# Wiegand.net
KiCad netlist of a schematic drawn in EAGLE
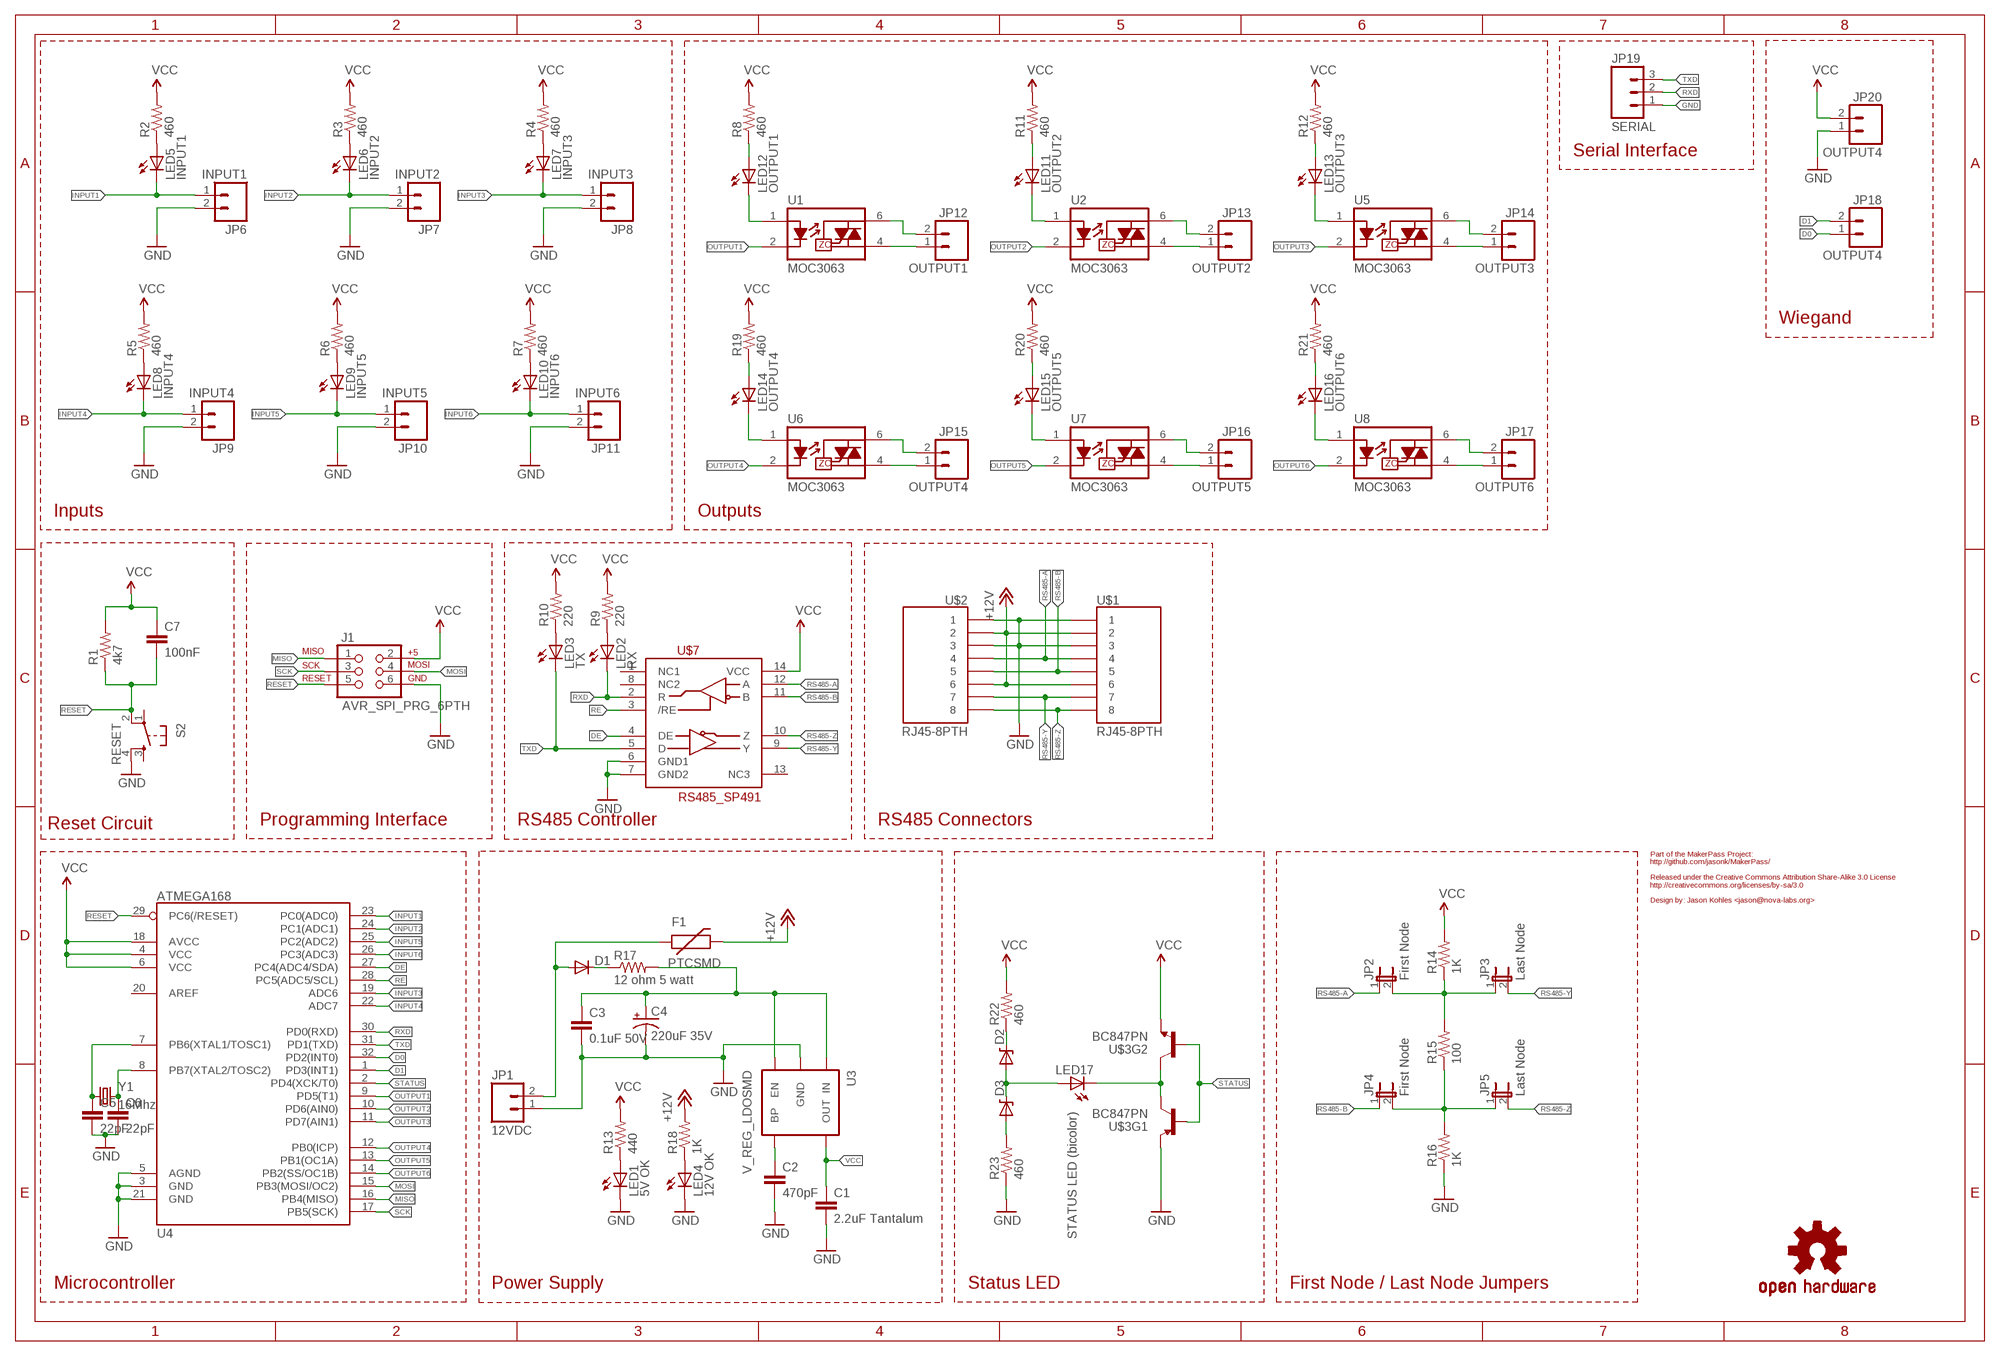
[diagram p0: schematic, sheet 1]

(export (version "E")
  (design (tool "Eeschema 10.0.6"))
  (components
    (comp (ref "C1")
      (value "2.2uF Tantalum")
      (footprint "eagle-import:0402-CAP")
      (libsource (lib "eagle-import") (part "CAP0402-CAP"))
    )
    (comp (ref "C2")
      (value "470pF")
      (footprint "eagle-import:0402-CAP")
      (libsource (lib "eagle-import") (part "CAP0402-CAP"))
    )
    (comp (ref "C3")
      (value "0.1uF 50V")
      (footprint "eagle-import:0402-CAP")
      (libsource (lib "eagle-import") (part "CAP0402-CAP"))
    )
    (comp (ref "C4")
      (value "220uF 35V")
      (footprint "eagle-import:VISHAY_C")
      (libsource (lib "eagle-import") (part "CAP_POLSMD"))
    )
    (comp (ref "C5")
      (value "22pF")
      (footprint "eagle-import:0603-CAP")
      (libsource (lib "eagle-import") (part "CAP0603-CAP"))
    )
    (comp (ref "C6")
      (value "22pF")
      (footprint "eagle-import:0603-CAP")
      (libsource (lib "eagle-import") (part "CAP0603-CAP"))
    )
    (comp (ref "C7")
      (value "100nF")
      (footprint "eagle-import:0603-CAP")
      (libsource (lib "eagle-import") (part "CAP0603-CAP"))
    )
    (comp (ref "D1")
      (value "DIODESMA")
      (footprint "eagle-import:SMA-DIODE")
      (libsource (lib "eagle-import") (part "DIODESMA"))
    )
    (comp (ref "D2")
      (value "DIODE-ZENER-BZT52")
      (footprint "eagle-import:SOD-323")
      (libsource (lib "eagle-import") (part "DIODE-ZENER-BZT52"))
    )
    (comp (ref "D3")
      (value "DIODE-ZENER-BZT52")
      (footprint "eagle-import:SOD-323")
      (libsource (lib "eagle-import") (part "DIODE-ZENER-BZT52"))
    )
    (comp (ref "F1")
      (value "PTCSMD")
      (footprint "eagle-import:PTC-1206")
      (libsource (lib "eagle-import") (part "PTCSMD"))
    )
    (comp (ref "J1")
      (value "AVR_SPI_PRG_6PTH")
      (footprint "eagle-import:2X3")
      (libsource (lib "eagle-import") (part "AVR_SPI_PRG_6PTH"))
    )
    (comp (ref "JP1")
      (value "12VDC")
      (footprint "eagle-import:SCREWTERMINAL-5MM-2")
      (libsource (lib "eagle-import") (part "M025MM"))
    )
    (comp (ref "JP2")
      (value "First Node")
      (footprint "eagle-import:1X02")
      (libsource (lib "eagle-import") (part "JUMPER-2PTH"))
    )
    (comp (ref "JP3")
      (value "Last Node")
      (footprint "eagle-import:1X02")
      (libsource (lib "eagle-import") (part "JUMPER-2PTH"))
    )
    (comp (ref "JP4")
      (value "First Node")
      (footprint "eagle-import:1X02")
      (libsource (lib "eagle-import") (part "JUMPER-2PTH"))
    )
    (comp (ref "JP5")
      (value "Last Node")
      (footprint "eagle-import:1X02")
      (libsource (lib "eagle-import") (part "JUMPER-2PTH"))
    )
    (comp (ref "JP6")
      (value "INPUT1")
      (footprint "eagle-import:SCREWTERMINAL-3.5MM-2")
      (libsource (lib "eagle-import") (part "M023.5MM"))
    )
    (comp (ref "JP7")
      (value "INPUT2")
      (footprint "eagle-import:SCREWTERMINAL-3.5MM-2")
      (libsource (lib "eagle-import") (part "M023.5MM"))
    )
    (comp (ref "JP8")
      (value "INPUT3")
      (footprint "eagle-import:SCREWTERMINAL-3.5MM-2")
      (libsource (lib "eagle-import") (part "M023.5MM"))
    )
    (comp (ref "JP9")
      (value "INPUT4")
      (footprint "eagle-import:SCREWTERMINAL-3.5MM-2")
      (libsource (lib "eagle-import") (part "M023.5MM"))
    )
    (comp (ref "JP10")
      (value "INPUT5")
      (footprint "eagle-import:SCREWTERMINAL-3.5MM-2")
      (libsource (lib "eagle-import") (part "M023.5MM"))
    )
    (comp (ref "JP11")
      (value "INPUT6")
      (footprint "eagle-import:SCREWTERMINAL-3.5MM-2")
      (libsource (lib "eagle-import") (part "M023.5MM"))
    )
    (comp (ref "JP12")
      (value "OUTPUT1")
      (footprint "eagle-import:SCREWTERMINAL-3.5MM-2")
      (libsource (lib "eagle-import") (part "M023.5MM"))
    )
    (comp (ref "JP13")
      (value "OUTPUT2")
      (footprint "eagle-import:SCREWTERMINAL-3.5MM-2")
      (libsource (lib "eagle-import") (part "M023.5MM"))
    )
    (comp (ref "JP14")
      (value "OUTPUT3")
      (footprint "eagle-import:SCREWTERMINAL-3.5MM-2")
      (libsource (lib "eagle-import") (part "M023.5MM"))
    )
    (comp (ref "JP15")
      (value "OUTPUT4")
      (footprint "eagle-import:SCREWTERMINAL-3.5MM-2")
      (libsource (lib "eagle-import") (part "M023.5MM"))
    )
    (comp (ref "JP16")
      (value "OUTPUT5")
      (footprint "eagle-import:SCREWTERMINAL-3.5MM-2")
      (libsource (lib "eagle-import") (part "M023.5MM"))
    )
    (comp (ref "JP17")
      (value "OUTPUT6")
      (footprint "eagle-import:SCREWTERMINAL-3.5MM-2")
      (libsource (lib "eagle-import") (part "M023.5MM"))
    )
    (comp (ref "JP18")
      (value "OUTPUT4")
      (footprint "eagle-import:SCREWTERMINAL-3.5MM-2")
      (libsource (lib "eagle-import") (part "M023.5MM"))
    )
    (comp (ref "JP19")
      (value "SERIAL")
      (footprint "eagle-import:1X03")
      (libsource (lib "eagle-import") (part "M03PTH"))
    )
    (comp (ref "JP20")
      (value "OUTPUT4")
      (footprint "eagle-import:SCREWTERMINAL-3.5MM-2")
      (libsource (lib "eagle-import") (part "M023.5MM"))
    )
    (comp (ref "LED1")
      (value "5V OK")
      (footprint "eagle-import:LED-1206")
      (libsource (lib "eagle-import") (part "LED1206"))
    )
    (comp (ref "LED2")
      (value "RX")
      (footprint "eagle-import:LED-1206")
      (libsource (lib "eagle-import") (part "LED1206"))
    )
    (comp (ref "LED3")
      (value "TX")
      (footprint "eagle-import:LED-1206")
      (libsource (lib "eagle-import") (part "LED1206"))
    )
    (comp (ref "LED4")
      (value "12V OK")
      (footprint "eagle-import:LED-1206")
      (libsource (lib "eagle-import") (part "LED1206"))
    )
    (comp (ref "LED5")
      (value "INPUT1")
      (footprint "eagle-import:LED-1206")
      (libsource (lib "eagle-import") (part "LED1206"))
    )
    (comp (ref "LED6")
      (value "INPUT2")
      (footprint "eagle-import:LED-1206")
      (libsource (lib "eagle-import") (part "LED1206"))
    )
    (comp (ref "LED7")
      (value "INPUT3")
      (footprint "eagle-import:LED-1206")
      (libsource (lib "eagle-import") (part "LED1206"))
    )
    (comp (ref "LED8")
      (value "INPUT4")
      (footprint "eagle-import:LED-1206")
      (libsource (lib "eagle-import") (part "LED1206"))
    )
    (comp (ref "LED9")
      (value "INPUT5")
      (footprint "eagle-import:LED-1206")
      (libsource (lib "eagle-import") (part "LED1206"))
    )
    (comp (ref "LED10")
      (value "INPUT6")
      (footprint "eagle-import:LED-1206")
      (libsource (lib "eagle-import") (part "LED1206"))
    )
    (comp (ref "LED11")
      (value "OUTPUT2")
      (footprint "eagle-import:LED-1206")
      (libsource (lib "eagle-import") (part "LED1206"))
    )
    (comp (ref "LED12")
      (value "OUTPUT1")
      (footprint "eagle-import:LED-1206")
      (libsource (lib "eagle-import") (part "LED1206"))
    )
    (comp (ref "LED13")
      (value "OUTPUT3")
      (footprint "eagle-import:LED-1206")
      (libsource (lib "eagle-import") (part "LED1206"))
    )
    (comp (ref "LED14")
      (value "OUTPUT4")
      (footprint "eagle-import:LED-1206")
      (libsource (lib "eagle-import") (part "LED1206"))
    )
    (comp (ref "LED15")
      (value "OUTPUT5")
      (footprint "eagle-import:LED-1206")
      (libsource (lib "eagle-import") (part "LED1206"))
    )
    (comp (ref "LED16")
      (value "OUTPUT6")
      (footprint "eagle-import:LED-1206")
      (libsource (lib "eagle-import") (part "LED1206"))
    )
    (comp (ref "LED17")
      (value "STATUS LED (bicolor)")
      (footprint "eagle-import:LED-1206")
      (libsource (lib "eagle-import") (part "LED1206"))
    )
    (comp (ref "LOGO1")
      (value "OSHW-LOGOM")
      (footprint "eagle-import:OSHW-LOGO-M")
      (libsource (lib "eagle-import") (part "OSHW-LOGOM"))
    )
    (comp (ref "R1")
      (value "4k7")
      (footprint "eagle-import:0603-RES")
      (libsource (lib "eagle-import") (part "RESISTOR0603-RES"))
    )
    (comp (ref "R2")
      (value "460")
      (footprint "eagle-import:0603-RES")
      (libsource (lib "eagle-import") (part "RESISTOR0603-RES"))
    )
    (comp (ref "R3")
      (value "460")
      (footprint "eagle-import:0603-RES")
      (libsource (lib "eagle-import") (part "RESISTOR0603-RES"))
    )
    (comp (ref "R4")
      (value "460")
      (footprint "eagle-import:0603-RES")
      (libsource (lib "eagle-import") (part "RESISTOR0603-RES"))
    )
    (comp (ref "R5")
      (value "460")
      (footprint "eagle-import:0603-RES")
      (libsource (lib "eagle-import") (part "RESISTOR0603-RES"))
    )
    (comp (ref "R6")
      (value "460")
      (footprint "eagle-import:0603-RES")
      (libsource (lib "eagle-import") (part "RESISTOR0603-RES"))
    )
    (comp (ref "R7")
      (value "460")
      (footprint "eagle-import:0603-RES")
      (libsource (lib "eagle-import") (part "RESISTOR0603-RES"))
    )
    (comp (ref "R8")
      (value "460")
      (footprint "eagle-import:0603-RES")
      (libsource (lib "eagle-import") (part "RESISTOR0603-RES"))
    )
    (comp (ref "R9")
      (value "220")
      (footprint "eagle-import:0603-RES")
      (libsource (lib "eagle-import") (part "RESISTOR0603-RES"))
    )
    (comp (ref "R10")
      (value "220")
      (footprint "eagle-import:0603-RES")
      (libsource (lib "eagle-import") (part "RESISTOR0603-RES"))
    )
    (comp (ref "R11")
      (value "460")
      (footprint "eagle-import:0603-RES")
      (libsource (lib "eagle-import") (part "RESISTOR0603-RES"))
    )
    (comp (ref "R12")
      (value "460")
      (footprint "eagle-import:0603-RES")
      (libsource (lib "eagle-import") (part "RESISTOR0603-RES"))
    )
    (comp (ref "R13")
      (value "440")
      (footprint "eagle-import:0603-RES")
      (libsource (lib "eagle-import") (part "RESISTOR0603-RES"))
    )
    (comp (ref "R14")
      (value "1K")
      (footprint "eagle-import:0603-RES")
      (libsource (lib "eagle-import") (part "RESISTOR0603-RES"))
    )
    (comp (ref "R15")
      (value "100")
      (footprint "eagle-import:0603-RES")
      (libsource (lib "eagle-import") (part "RESISTOR0603-RES"))
    )
    (comp (ref "R16")
      (value "1K")
      (footprint "eagle-import:0603-RES")
      (libsource (lib "eagle-import") (part "RESISTOR0603-RES"))
    )
    (comp (ref "R17")
      (value "12 ohm 5 watt")
      (footprint "eagle-import:0603-RES")
      (libsource (lib "eagle-import") (part "RESISTOR0603-RES"))
    )
    (comp (ref "R18")
      (value "1K")
      (footprint "eagle-import:0603-RES")
      (libsource (lib "eagle-import") (part "RESISTOR0603-RES"))
    )
    (comp (ref "R19")
      (value "460")
      (footprint "eagle-import:0603-RES")
      (libsource (lib "eagle-import") (part "RESISTOR0603-RES"))
    )
    (comp (ref "R20")
      (value "460")
      (footprint "eagle-import:0603-RES")
      (libsource (lib "eagle-import") (part "RESISTOR0603-RES"))
    )
    (comp (ref "R21")
      (value "460")
      (footprint "eagle-import:0603-RES")
      (libsource (lib "eagle-import") (part "RESISTOR0603-RES"))
    )
    (comp (ref "R22")
      (value "460")
      (footprint "eagle-import:0603-RES")
      (libsource (lib "eagle-import") (part "RESISTOR0603-RES"))
    )
    (comp (ref "R23")
      (value "460")
      (footprint "eagle-import:0603-RES")
      (libsource (lib "eagle-import") (part "RESISTOR0603-RES"))
    )
    (comp (ref "S2")
      (value "RESET")
      (footprint "eagle-import:TACTILE_SWITCH_SMD")
      (libsource (lib "eagle-import") (part "TAC_SWITCHSMD"))
    )
    (comp (ref "U$1")
      (value "RJ45-8PTH")
      (footprint "eagle-import:RJ45-8")
      (libsource (lib "eagle-import") (part "RJ45-8PTH"))
    )
    (comp (ref "U$2")
      (value "RJ45-8PTH")
      (footprint "eagle-import:RJ45-8")
      (libsource (lib "eagle-import") (part "RJ45-8PTH"))
    )
    (comp (ref "U$3")
      (value "BC847PN")
      (footprint "eagle-import:SOT363")
      (libsource (lib "eagle-import") (part "BC847PN"))
    )
    (comp (ref "U$7")
      (value "RS485_SP491")
      (footprint "eagle-import:SOIC-14")
      (libsource (lib "eagle-import") (part "RS485_SP491"))
    )
    (comp (ref "U1")
      (value "MOC3063")
      (footprint "eagle-import:DIP8SMD")
      (libsource (lib "eagle-import") (part "MOC3063S"))
    )
    (comp (ref "U2")
      (value "MOC3063")
      (footprint "eagle-import:DIP8SMD")
      (libsource (lib "eagle-import") (part "MOC3063S"))
    )
    (comp (ref "U3")
      (value "V_REG_LDOSMD")
      (footprint "eagle-import:SOT23-5")
      (libsource (lib "eagle-import") (part "V_REG_LDOSMD"))
    )
    (comp (ref "U4")
      (value "ATMEGA168")
      (footprint "eagle-import:TQFP32-08")
      (libsource (lib "eagle-import") (part "ATMEGA168"))
    )
    (comp (ref "U5")
      (value "MOC3063")
      (footprint "eagle-import:DIP8SMD")
      (libsource (lib "eagle-import") (part "MOC3063S"))
    )
    (comp (ref "U6")
      (value "MOC3063")
      (footprint "eagle-import:DIP8SMD")
      (libsource (lib "eagle-import") (part "MOC3063S"))
    )
    (comp (ref "U7")
      (value "MOC3063")
      (footprint "eagle-import:DIP8SMD")
      (libsource (lib "eagle-import") (part "MOC3063S"))
    )
    (comp (ref "U8")
      (value "MOC3063")
      (footprint "eagle-import:DIP8SMD")
      (libsource (lib "eagle-import") (part "MOC3063S"))
    )
    (comp (ref "Y1")
      (value "16Mhz")
      (footprint "eagle-import:HC49UP")
      (libsource (lib "eagle-import") (part "CRYSTALSMD"))
    )
  )
  (nets
    (net (code "1") (name "+12V") (class "Default")
      (node (ref "F1") (pin "2") (pinfunction "2_2") (pintype "bidirectional"))
      (node (ref "R18") (pin "2") (pinfunction "2_2") (pintype "passive"))
      (node (ref "U$1") (pin "2") (pinfunction "2_2") (pintype "bidirectional"))
      (node (ref "U$1") (pin "6") (pinfunction "6_6") (pintype "bidirectional"))
      (node (ref "U$2") (pin "2") (pinfunction "2_2") (pintype "bidirectional"))
      (node (ref "U$2") (pin "6") (pinfunction "6_6") (pintype "bidirectional"))
    )
    (net (code "2") (name "D0") (class "Default")
      (node (ref "JP18") (pin "1") (pinfunction "1_1") (pintype "passive"))
      (node (ref "U4") (pin "32") (pinfunction "PD2(INT0)_32") (pintype "bidirectional"))
    )
    (net (code "3") (name "D1") (class "Default")
      (node (ref "JP18") (pin "2") (pinfunction "2_2") (pintype "passive"))
      (node (ref "U4") (pin "1") (pinfunction "PD3(INT1)_1") (pintype "bidirectional"))
    )
    (net (code "4") (name "DE") (class "Default")
      (node (ref "U$7") (pin "4") (pinfunction "DE_4") (pintype "bidirectional"))
      (node (ref "U4") (pin "27") (pinfunction "PC4(ADC4/SDA)_27") (pintype "bidirectional"))
    )
    (net (code "5") (name "GND") (class "Default")
      (node (ref "C1") (pin "2") (pinfunction "2_2") (pintype "passive"))
      (node (ref "C2") (pin "2") (pinfunction "2_2") (pintype "passive"))
      (node (ref "C3") (pin "2") (pinfunction "2_2") (pintype "passive"))
      (node (ref "C4") (pin "-") (pinfunction "-_-") (pintype "passive"))
      (node (ref "C5") (pin "2") (pinfunction "2_2") (pintype "passive"))
      (node (ref "C6") (pin "2") (pinfunction "2_2") (pintype "passive"))
      (node (ref "J1") (pin "6") (pinfunction "6_6") (pintype "passive"))
      (node (ref "JP1") (pin "1") (pinfunction "1_1") (pintype "passive"))
      (node (ref "JP10") (pin "2") (pinfunction "2_2") (pintype "passive"))
      (node (ref "JP11") (pin "2") (pinfunction "2_2") (pintype "passive"))
      (node (ref "JP19") (pin "1") (pinfunction "1_1") (pintype "passive"))
      (node (ref "JP20") (pin "1") (pinfunction "1_1") (pintype "passive"))
      (node (ref "JP6") (pin "2") (pinfunction "2_2") (pintype "passive"))
      (node (ref "JP7") (pin "2") (pinfunction "2_2") (pintype "passive"))
      (node (ref "JP8") (pin "2") (pinfunction "2_2") (pintype "passive"))
      (node (ref "JP9") (pin "2") (pinfunction "2_2") (pintype "passive"))
      (node (ref "LED1") (pin "C") (pinfunction "C_C") (pintype "passive"))
      (node (ref "LED4") (pin "C") (pinfunction "C_C") (pintype "passive"))
      (node (ref "R16") (pin "1") (pinfunction "1_1") (pintype "passive"))
      (node (ref "R23") (pin "1") (pinfunction "1_1") (pintype "passive"))
      (node (ref "S2") (pin "4") (pinfunction "4_4") (pintype "passive"))
      (node (ref "U$1") (pin "1") (pinfunction "1_1") (pintype "bidirectional"))
      (node (ref "U$1") (pin "3") (pinfunction "3_3") (pintype "bidirectional"))
      (node (ref "U$2") (pin "1") (pinfunction "1_1") (pintype "bidirectional"))
      (node (ref "U$2") (pin "3") (pinfunction "3_3") (pintype "bidirectional"))
      (node (ref "U$3") (pin "1") (pinfunction "E_1") (pintype "passive"))
      (node (ref "U$7") (pin "6") (pinfunction "GND1_6") (pintype "bidirectional"))
      (node (ref "U$7") (pin "7") (pinfunction "GND2_7") (pintype "bidirectional"))
      (node (ref "U3") (pin "2") (pinfunction "GND_2") (pintype "input"))
      (node (ref "U4") (pin "21") (pinfunction "GND_21") (pintype "bidirectional"))
      (node (ref "U4") (pin "3") (pinfunction "GND_3") (pintype "bidirectional"))
      (node (ref "U4") (pin "5") (pinfunction "AGND_5") (pintype "bidirectional"))
    )
    (net (code "6") (name "INPUT1") (class "Default")
      (node (ref "JP6") (pin "1") (pinfunction "1_1") (pintype "passive"))
      (node (ref "LED5") (pin "C") (pinfunction "C_C") (pintype "passive"))
      (node (ref "U4") (pin "23") (pinfunction "PC0(ADC0)_23") (pintype "bidirectional"))
    )
    (net (code "7") (name "INPUT2") (class "Default")
      (node (ref "JP7") (pin "1") (pinfunction "1_1") (pintype "passive"))
      (node (ref "LED6") (pin "C") (pinfunction "C_C") (pintype "passive"))
      (node (ref "U4") (pin "24") (pinfunction "PC1(ADC1)_24") (pintype "bidirectional"))
    )
    (net (code "8") (name "INPUT3") (class "Default")
      (node (ref "JP8") (pin "1") (pinfunction "1_1") (pintype "passive"))
      (node (ref "LED7") (pin "C") (pinfunction "C_C") (pintype "passive"))
      (node (ref "U4") (pin "19") (pinfunction "ADC6_19") (pintype "bidirectional"))
    )
    (net (code "9") (name "INPUT4") (class "Default")
      (node (ref "JP9") (pin "1") (pinfunction "1_1") (pintype "passive"))
      (node (ref "LED8") (pin "C") (pinfunction "C_C") (pintype "passive"))
      (node (ref "U4") (pin "22") (pinfunction "ADC7_22") (pintype "bidirectional"))
    )
    (net (code "10") (name "INPUT5") (class "Default")
      (node (ref "JP10") (pin "1") (pinfunction "1_1") (pintype "passive"))
      (node (ref "LED9") (pin "C") (pinfunction "C_C") (pintype "passive"))
      (node (ref "U4") (pin "25") (pinfunction "PC2(ADC2)_25") (pintype "bidirectional"))
    )
    (net (code "11") (name "INPUT6") (class "Default")
      (node (ref "JP11") (pin "1") (pinfunction "1_1") (pintype "passive"))
      (node (ref "LED10") (pin "C") (pinfunction "C_C") (pintype "passive"))
      (node (ref "U4") (pin "26") (pinfunction "PC3(ADC3)_26") (pintype "bidirectional"))
    )
    (net (code "12") (name "MISO") (class "Default")
      (node (ref "J1") (pin "1") (pinfunction "1_1") (pintype "passive"))
      (node (ref "U4") (pin "16") (pinfunction "PB4(MISO)_16") (pintype "bidirectional"))
    )
    (net (code "13") (name "MOSI") (class "Default")
      (node (ref "J1") (pin "4") (pinfunction "4_4") (pintype "passive"))
      (node (ref "U4") (pin "15") (pinfunction "PB3(MOSI/OC2)_15") (pintype "bidirectional"))
    )
    (net (code "14") (name "Net-(D1-PadA)") (class "Default")
      (node (ref "D1") (pin "A") (pinfunction "A_A") (pintype "passive"))
      (node (ref "F1") (pin "1") (pinfunction "1_1") (pintype "bidirectional"))
      (node (ref "JP1") (pin "2") (pinfunction "2_2") (pintype "passive"))
    )
    (net (code "15") (name "Net-(D1-PadC)") (class "Default")
      (node (ref "D1") (pin "C") (pinfunction "C_C") (pintype "passive"))
      (node (ref "R17") (pin "1") (pinfunction "1_1") (pintype "passive"))
    )
    (net (code "16") (name "Net-(D2-A)") (class "Default")
      (node (ref "D2") (pin "2") (pinfunction "A_2") (pintype "passive"))
      (node (ref "D3") (pin "1") (pinfunction "C_1") (pintype "passive"))
      (node (ref "LED17") (pin "A") (pinfunction "A_A") (pintype "passive"))
    )
    (net (code "17") (name "Net-(D2-C)") (class "Default")
      (node (ref "D2") (pin "1") (pinfunction "C_1") (pintype "passive"))
      (node (ref "R22") (pin "1") (pinfunction "1_1") (pintype "passive"))
    )
    (net (code "18") (name "Net-(D3-A)") (class "Default")
      (node (ref "D3") (pin "2") (pinfunction "A_2") (pintype "passive"))
      (node (ref "R23") (pin "2") (pinfunction "2_2") (pintype "passive"))
    )
    (net (code "19") (name "Net-(JP2-Pad2)") (class "Default")
      (node (ref "JP2") (pin "2") (pinfunction "2_2") (pintype "passive"))
      (node (ref "JP3") (pin "1") (pinfunction "1_1") (pintype "passive"))
      (node (ref "R14") (pin "1") (pinfunction "1_1") (pintype "passive"))
      (node (ref "R15") (pin "2") (pinfunction "2_2") (pintype "passive"))
    )
    (net (code "20") (name "Net-(JP4-Pad2)") (class "Default")
      (node (ref "JP4") (pin "2") (pinfunction "2_2") (pintype "passive"))
      (node (ref "JP5") (pin "1") (pinfunction "1_1") (pintype "passive"))
      (node (ref "R15") (pin "1") (pinfunction "1_1") (pintype "passive"))
      (node (ref "R16") (pin "2") (pinfunction "2_2") (pintype "passive"))
    )
    (net (code "21") (name "Net-(LED1-PadA)") (class "Default")
      (node (ref "LED1") (pin "A") (pinfunction "A_A") (pintype "passive"))
      (node (ref "R13") (pin "1") (pinfunction "1_1") (pintype "passive"))
    )
    (net (code "22") (name "Net-(LED2-PadA)") (class "Default")
      (node (ref "LED2") (pin "A") (pinfunction "A_A") (pintype "passive"))
      (node (ref "R9") (pin "1") (pinfunction "1_1") (pintype "passive"))
    )
    (net (code "23") (name "Net-(LED3-PadA)") (class "Default")
      (node (ref "LED3") (pin "A") (pinfunction "A_A") (pintype "passive"))
      (node (ref "R10") (pin "1") (pinfunction "1_1") (pintype "passive"))
    )
    (net (code "24") (name "Net-(LED4-PadA)") (class "Default")
      (node (ref "LED4") (pin "A") (pinfunction "A_A") (pintype "passive"))
      (node (ref "R18") (pin "1") (pinfunction "1_1") (pintype "passive"))
    )
    (net (code "25") (name "Net-(LED5-PadA)") (class "Default")
      (node (ref "LED5") (pin "A") (pinfunction "A_A") (pintype "passive"))
      (node (ref "R2") (pin "1") (pinfunction "1_1") (pintype "passive"))
    )
    (net (code "26") (name "Net-(LED6-PadA)") (class "Default")
      (node (ref "LED6") (pin "A") (pinfunction "A_A") (pintype "passive"))
      (node (ref "R3") (pin "1") (pinfunction "1_1") (pintype "passive"))
    )
    (net (code "27") (name "Net-(LED7-PadA)") (class "Default")
      (node (ref "LED7") (pin "A") (pinfunction "A_A") (pintype "passive"))
      (node (ref "R4") (pin "1") (pinfunction "1_1") (pintype "passive"))
    )
    (net (code "28") (name "Net-(LED8-PadA)") (class "Default")
      (node (ref "LED8") (pin "A") (pinfunction "A_A") (pintype "passive"))
      (node (ref "R5") (pin "1") (pinfunction "1_1") (pintype "passive"))
    )
    (net (code "29") (name "Net-(LED9-PadA)") (class "Default")
      (node (ref "LED9") (pin "A") (pinfunction "A_A") (pintype "passive"))
      (node (ref "R6") (pin "1") (pinfunction "1_1") (pintype "passive"))
    )
    (net (code "30") (name "Net-(LED10-PadA)") (class "Default")
      (node (ref "LED10") (pin "A") (pinfunction "A_A") (pintype "passive"))
      (node (ref "R7") (pin "1") (pinfunction "1_1") (pintype "passive"))
    )
    (net (code "31") (name "Net-(LED11-PadA)") (class "Default")
      (node (ref "LED11") (pin "A") (pinfunction "A_A") (pintype "passive"))
      (node (ref "R11") (pin "1") (pinfunction "1_1") (pintype "passive"))
    )
    (net (code "32") (name "Net-(LED12-PadA)") (class "Default")
      (node (ref "LED12") (pin "A") (pinfunction "A_A") (pintype "passive"))
      (node (ref "R8") (pin "1") (pinfunction "1_1") (pintype "passive"))
    )
    (net (code "33") (name "Net-(LED13-PadA)") (class "Default")
      (node (ref "LED13") (pin "A") (pinfunction "A_A") (pintype "passive"))
      (node (ref "R12") (pin "1") (pinfunction "1_1") (pintype "passive"))
    )
    (net (code "34") (name "Net-(LED14-PadA)") (class "Default")
      (node (ref "LED14") (pin "A") (pinfunction "A_A") (pintype "passive"))
      (node (ref "R19") (pin "1") (pinfunction "1_1") (pintype "passive"))
    )
    (net (code "35") (name "Net-(LED15-PadA)") (class "Default")
      (node (ref "LED15") (pin "A") (pinfunction "A_A") (pintype "passive"))
      (node (ref "R20") (pin "1") (pinfunction "1_1") (pintype "passive"))
    )
    (net (code "36") (name "Net-(LED16-PadA)") (class "Default")
      (node (ref "LED16") (pin "A") (pinfunction "A_A") (pintype "passive"))
      (node (ref "R21") (pin "1") (pinfunction "1_1") (pintype "passive"))
    )
    (net (code "37") (name "Net-(U$3A-C)") (class "Default")
      (node (ref "LED17") (pin "C") (pinfunction "C_C") (pintype "passive"))
      (node (ref "U$3") (pin "3") (pinfunction "C_3") (pintype "passive"))
      (node (ref "U$3") (pin "6") (pinfunction "C_6") (pintype "passive"))
    )
    (net (code "38") (name "Net-(U1-A)") (class "Default")
      (node (ref "LED12") (pin "C") (pinfunction "C_C") (pintype "passive"))
      (node (ref "U1") (pin "1") (pinfunction "A_1") (pintype "bidirectional"))
    )
    (net (code "39") (name "Net-(U1-T1)") (class "Default")
      (node (ref "JP12") (pin "2") (pinfunction "2_2") (pintype "passive"))
      (node (ref "U1") (pin "6") (pinfunction "T1_6") (pintype "bidirectional"))
    )
    (net (code "40") (name "Net-(U1-T2)") (class "Default")
      (node (ref "JP12") (pin "1") (pinfunction "1_1") (pintype "passive"))
      (node (ref "U1") (pin "4") (pinfunction "T2_4") (pintype "bidirectional"))
    )
    (net (code "41") (name "Net-(U2-A)") (class "Default")
      (node (ref "LED11") (pin "C") (pinfunction "C_C") (pintype "passive"))
      (node (ref "U2") (pin "1") (pinfunction "A_1") (pintype "bidirectional"))
    )
    (net (code "42") (name "Net-(U2-T1)") (class "Default")
      (node (ref "JP13") (pin "2") (pinfunction "2_2") (pintype "passive"))
      (node (ref "U2") (pin "6") (pinfunction "T1_6") (pintype "bidirectional"))
    )
    (net (code "43") (name "Net-(U2-T2)") (class "Default")
      (node (ref "JP13") (pin "1") (pinfunction "1_1") (pintype "passive"))
      (node (ref "U2") (pin "4") (pinfunction "T2_4") (pintype "bidirectional"))
    )
    (net (code "44") (name "Net-(U3-BP)") (class "Default")
      (node (ref "C2") (pin "1") (pinfunction "1_1") (pintype "passive"))
      (node (ref "U3") (pin "4") (pinfunction "BP_4") (pintype "input"))
    )
    (net (code "45") (name "Net-(U3-EN)") (class "Default")
      (node (ref "C3") (pin "1") (pinfunction "1_1") (pintype "passive"))
      (node (ref "C4") (pin "+") (pinfunction "+_+") (pintype "passive"))
      (node (ref "R17") (pin "2") (pinfunction "2_2") (pintype "passive"))
      (node (ref "U3") (pin "1") (pinfunction "IN_1") (pintype "input"))
      (node (ref "U3") (pin "3") (pinfunction "EN_3") (pintype "input"))
    )
    (net (code "46") (name "Net-(U4-PB6(XTAL1{slash}TOSC1))") (class "Default")
      (node (ref "C5") (pin "1") (pinfunction "1_1") (pintype "passive"))
      (node (ref "U4") (pin "7") (pinfunction "PB6(XTAL1/TOSC1)_7") (pintype "bidirectional"))
      (node (ref "Y1") (pin "1") (pinfunction "1_1") (pintype "passive"))
    )
    (net (code "47") (name "Net-(U4-PB7(XTAL2{slash}TOSC2))") (class "Default")
      (node (ref "C6") (pin "1") (pinfunction "1_1") (pintype "passive"))
      (node (ref "U4") (pin "8") (pinfunction "PB7(XTAL2/TOSC2)_8") (pintype "bidirectional"))
      (node (ref "Y1") (pin "2") (pinfunction "2_2") (pintype "passive"))
    )
    (net (code "48") (name "Net-(U5-A)") (class "Default")
      (node (ref "LED13") (pin "C") (pinfunction "C_C") (pintype "passive"))
      (node (ref "U5") (pin "1") (pinfunction "A_1") (pintype "bidirectional"))
    )
    (net (code "49") (name "Net-(U5-T1)") (class "Default")
      (node (ref "JP14") (pin "2") (pinfunction "2_2") (pintype "passive"))
      (node (ref "U5") (pin "6") (pinfunction "T1_6") (pintype "bidirectional"))
    )
    (net (code "50") (name "Net-(U5-T2)") (class "Default")
      (node (ref "JP14") (pin "1") (pinfunction "1_1") (pintype "passive"))
      (node (ref "U5") (pin "4") (pinfunction "T2_4") (pintype "bidirectional"))
    )
    (net (code "51") (name "Net-(U6-A)") (class "Default")
      (node (ref "LED14") (pin "C") (pinfunction "C_C") (pintype "passive"))
      (node (ref "U6") (pin "1") (pinfunction "A_1") (pintype "bidirectional"))
    )
    (net (code "52") (name "Net-(U6-T1)") (class "Default")
      (node (ref "JP15") (pin "2") (pinfunction "2_2") (pintype "passive"))
      (node (ref "U6") (pin "6") (pinfunction "T1_6") (pintype "bidirectional"))
    )
    (net (code "53") (name "Net-(U6-T2)") (class "Default")
      (node (ref "JP15") (pin "1") (pinfunction "1_1") (pintype "passive"))
      (node (ref "U6") (pin "4") (pinfunction "T2_4") (pintype "bidirectional"))
    )
    (net (code "54") (name "Net-(U7-A)") (class "Default")
      (node (ref "LED15") (pin "C") (pinfunction "C_C") (pintype "passive"))
      (node (ref "U7") (pin "1") (pinfunction "A_1") (pintype "bidirectional"))
    )
    (net (code "55") (name "Net-(U7-T1)") (class "Default")
      (node (ref "JP16") (pin "2") (pinfunction "2_2") (pintype "passive"))
      (node (ref "U7") (pin "6") (pinfunction "T1_6") (pintype "bidirectional"))
    )
    (net (code "56") (name "Net-(U7-T2)") (class "Default")
      (node (ref "JP16") (pin "1") (pinfunction "1_1") (pintype "passive"))
      (node (ref "U7") (pin "4") (pinfunction "T2_4") (pintype "bidirectional"))
    )
    (net (code "57") (name "Net-(U8-A)") (class "Default")
      (node (ref "LED16") (pin "C") (pinfunction "C_C") (pintype "passive"))
      (node (ref "U8") (pin "1") (pinfunction "A_1") (pintype "bidirectional"))
    )
    (net (code "58") (name "Net-(U8-T1)") (class "Default")
      (node (ref "JP17") (pin "2") (pinfunction "2_2") (pintype "passive"))
      (node (ref "U8") (pin "6") (pinfunction "T1_6") (pintype "bidirectional"))
    )
    (net (code "59") (name "Net-(U8-T2)") (class "Default")
      (node (ref "JP17") (pin "1") (pinfunction "1_1") (pintype "passive"))
      (node (ref "U8") (pin "4") (pinfunction "T2_4") (pintype "bidirectional"))
    )
    (net (code "60") (name "OUTPUT1") (class "Default")
      (node (ref "U1") (pin "2") (pinfunction "K_2") (pintype "bidirectional"))
      (node (ref "U4") (pin "9") (pinfunction "PD5(T1)_9") (pintype "bidirectional"))
    )
    (net (code "61") (name "OUTPUT2") (class "Default")
      (node (ref "U2") (pin "2") (pinfunction "K_2") (pintype "bidirectional"))
      (node (ref "U4") (pin "10") (pinfunction "PD6(AIN0)_10") (pintype "bidirectional"))
    )
    (net (code "62") (name "OUTPUT3") (class "Default")
      (node (ref "U4") (pin "11") (pinfunction "PD7(AIN1)_11") (pintype "bidirectional"))
      (node (ref "U5") (pin "2") (pinfunction "K_2") (pintype "bidirectional"))
    )
    (net (code "63") (name "OUTPUT4") (class "Default")
      (node (ref "U4") (pin "12") (pinfunction "PB0(ICP)_12") (pintype "bidirectional"))
      (node (ref "U6") (pin "2") (pinfunction "K_2") (pintype "bidirectional"))
    )
    (net (code "64") (name "OUTPUT5") (class "Default")
      (node (ref "U4") (pin "13") (pinfunction "PB1(OC1A)_13") (pintype "bidirectional"))
      (node (ref "U7") (pin "2") (pinfunction "K_2") (pintype "bidirectional"))
    )
    (net (code "65") (name "OUTPUT6") (class "Default")
      (node (ref "U4") (pin "14") (pinfunction "PB2(SS/OC1B)_14") (pintype "bidirectional"))
      (node (ref "U8") (pin "2") (pinfunction "K_2") (pintype "bidirectional"))
    )
    (net (code "66") (name "RE") (class "Default")
      (node (ref "U$7") (pin "3") (pinfunction "/RE_3") (pintype "bidirectional"))
      (node (ref "U4") (pin "28") (pinfunction "PC5(ADC5/SCL)_28") (pintype "bidirectional"))
    )
    (net (code "67") (name "RESET") (class "Default")
      (node (ref "C7") (pin "2") (pinfunction "2_2") (pintype "passive"))
      (node (ref "J1") (pin "5") (pinfunction "5_5") (pintype "passive"))
      (node (ref "R1") (pin "1") (pinfunction "1_1") (pintype "passive"))
      (node (ref "S2") (pin "2") (pinfunction "2_2") (pintype "passive"))
      (node (ref "U4") (pin "29") (pinfunction "PC6(/RESET)_29") (pintype "bidirectional"))
    )
    (net (code "68") (name "RS485-A") (class "Default")
      (node (ref "JP2") (pin "1") (pinfunction "1_1") (pintype "passive"))
      (node (ref "U$1") (pin "4") (pinfunction "4_4") (pintype "bidirectional"))
      (node (ref "U$2") (pin "4") (pinfunction "4_4") (pintype "bidirectional"))
      (node (ref "U$7") (pin "12") (pinfunction "A_12") (pintype "bidirectional"))
    )
    (net (code "69") (name "RS485-B") (class "Default")
      (node (ref "JP4") (pin "1") (pinfunction "1_1") (pintype "passive"))
      (node (ref "U$1") (pin "5") (pinfunction "5_5") (pintype "bidirectional"))
      (node (ref "U$2") (pin "5") (pinfunction "5_5") (pintype "bidirectional"))
      (node (ref "U$7") (pin "11") (pinfunction "B_11") (pintype "bidirectional"))
    )
    (net (code "70") (name "RS485-Y") (class "Default")
      (node (ref "JP3") (pin "2") (pinfunction "2_2") (pintype "passive"))
      (node (ref "U$1") (pin "7") (pinfunction "7_7") (pintype "bidirectional"))
      (node (ref "U$2") (pin "7") (pinfunction "7_7") (pintype "bidirectional"))
      (node (ref "U$7") (pin "9") (pinfunction "Y_9") (pintype "bidirectional"))
    )
    (net (code "71") (name "RS485-Z") (class "Default")
      (node (ref "JP5") (pin "2") (pinfunction "2_2") (pintype "passive"))
      (node (ref "U$1") (pin "8") (pinfunction "8_8") (pintype "bidirectional"))
      (node (ref "U$2") (pin "8") (pinfunction "8_8") (pintype "bidirectional"))
      (node (ref "U$7") (pin "10") (pinfunction "Z_10") (pintype "bidirectional"))
    )
    (net (code "72") (name "RXD") (class "Default")
      (node (ref "JP19") (pin "2") (pinfunction "2_2") (pintype "passive"))
      (node (ref "LED2") (pin "C") (pinfunction "C_C") (pintype "passive"))
      (node (ref "U$7") (pin "2") (pinfunction "R_2") (pintype "bidirectional"))
      (node (ref "U4") (pin "30") (pinfunction "PD0(RXD)_30") (pintype "bidirectional"))
    )
    (net (code "73") (name "SCK") (class "Default")
      (node (ref "J1") (pin "3") (pinfunction "3_3") (pintype "passive"))
      (node (ref "U4") (pin "17") (pinfunction "PB5(SCK)_17") (pintype "bidirectional"))
    )
    (net (code "74") (name "STATUS") (class "Default")
      (node (ref "U$3") (pin "2") (pinfunction "B_2") (pintype "passive"))
      (node (ref "U$3") (pin "5") (pinfunction "B_5") (pintype "passive"))
      (node (ref "U4") (pin "2") (pinfunction "PD4(XCK/T0)_2") (pintype "bidirectional"))
    )
    (net (code "75") (name "TXD") (class "Default")
      (node (ref "JP19") (pin "3") (pinfunction "3_3") (pintype "passive"))
      (node (ref "LED3") (pin "C") (pinfunction "C_C") (pintype "passive"))
      (node (ref "U$7") (pin "5") (pinfunction "D_5") (pintype "bidirectional"))
      (node (ref "U4") (pin "31") (pinfunction "PD1(TXD)_31") (pintype "bidirectional"))
    )
    (net (code "76") (name "VCC") (class "Default")
      (node (ref "C1") (pin "1") (pinfunction "1_1") (pintype "passive"))
      (node (ref "C7") (pin "1") (pinfunction "1_1") (pintype "passive"))
      (node (ref "J1") (pin "2") (pinfunction "2_2") (pintype "passive"))
      (node (ref "JP20") (pin "2") (pinfunction "2_2") (pintype "passive"))
      (node (ref "R1") (pin "2") (pinfunction "2_2") (pintype "passive"))
      (node (ref "R10") (pin "2") (pinfunction "2_2") (pintype "passive"))
      (node (ref "R11") (pin "2") (pinfunction "2_2") (pintype "passive"))
      (node (ref "R12") (pin "2") (pinfunction "2_2") (pintype "passive"))
      (node (ref "R13") (pin "2") (pinfunction "2_2") (pintype "passive"))
      (node (ref "R14") (pin "2") (pinfunction "2_2") (pintype "passive"))
      (node (ref "R19") (pin "2") (pinfunction "2_2") (pintype "passive"))
      (node (ref "R2") (pin "2") (pinfunction "2_2") (pintype "passive"))
      (node (ref "R20") (pin "2") (pinfunction "2_2") (pintype "passive"))
      (node (ref "R21") (pin "2") (pinfunction "2_2") (pintype "passive"))
      (node (ref "R22") (pin "2") (pinfunction "2_2") (pintype "passive"))
      (node (ref "R3") (pin "2") (pinfunction "2_2") (pintype "passive"))
      (node (ref "R4") (pin "2") (pinfunction "2_2") (pintype "passive"))
      (node (ref "R5") (pin "2") (pinfunction "2_2") (pintype "passive"))
      (node (ref "R6") (pin "2") (pinfunction "2_2") (pintype "passive"))
      (node (ref "R7") (pin "2") (pinfunction "2_2") (pintype "passive"))
      (node (ref "R8") (pin "2") (pinfunction "2_2") (pintype "passive"))
      (node (ref "R9") (pin "2") (pinfunction "2_2") (pintype "passive"))
      (node (ref "U$3") (pin "4") (pinfunction "E_4") (pintype "passive"))
      (node (ref "U$7") (pin "14") (pinfunction "VCC_14") (pintype "bidirectional"))
      (node (ref "U3") (pin "5") (pinfunction "OUT_5") (pintype "passive"))
      (node (ref "U4") (pin "18") (pinfunction "AVCC_18") (pintype "bidirectional"))
      (node (ref "U4") (pin "4") (pinfunction "VCC_4") (pintype "bidirectional"))
      (node (ref "U4") (pin "6") (pinfunction "VCC_6") (pintype "bidirectional"))
    )
    (net (code "77") (name "unconnected-(S2-Pad1)") (class "Default")
      (node (ref "S2") (pin "1") (pinfunction "1_1") (pintype "passive"))
    )
    (net (code "78") (name "unconnected-(S2-Pad3)") (class "Default")
      (node (ref "S2") (pin "3") (pinfunction "3_3") (pintype "passive"))
    )
    (net (code "79") (name "unconnected-(U$7-NC1-Pad1)") (class "Default")
      (node (ref "U$7") (pin "1") (pinfunction "NC1_1") (pintype "bidirectional"))
    )
    (net (code "80") (name "unconnected-(U$7-NC2-Pad8)") (class "Default")
      (node (ref "U$7") (pin "8") (pinfunction "NC2_8") (pintype "bidirectional"))
    )
    (net (code "81") (name "unconnected-(U$7-NC3-Pad13)") (class "Default")
      (node (ref "U$7") (pin "13") (pinfunction "NC3_13") (pintype "bidirectional"))
    )
    (net (code "82") (name "unconnected-(U4-AREF-Pad20)") (class "Default")
      (node (ref "U4") (pin "20") (pinfunction "AREF_20") (pintype "bidirectional"))
    )
  )
)
